# Pg05__Platform_Power.net
KiCad netlist of a schematic drawn in Altium Designer
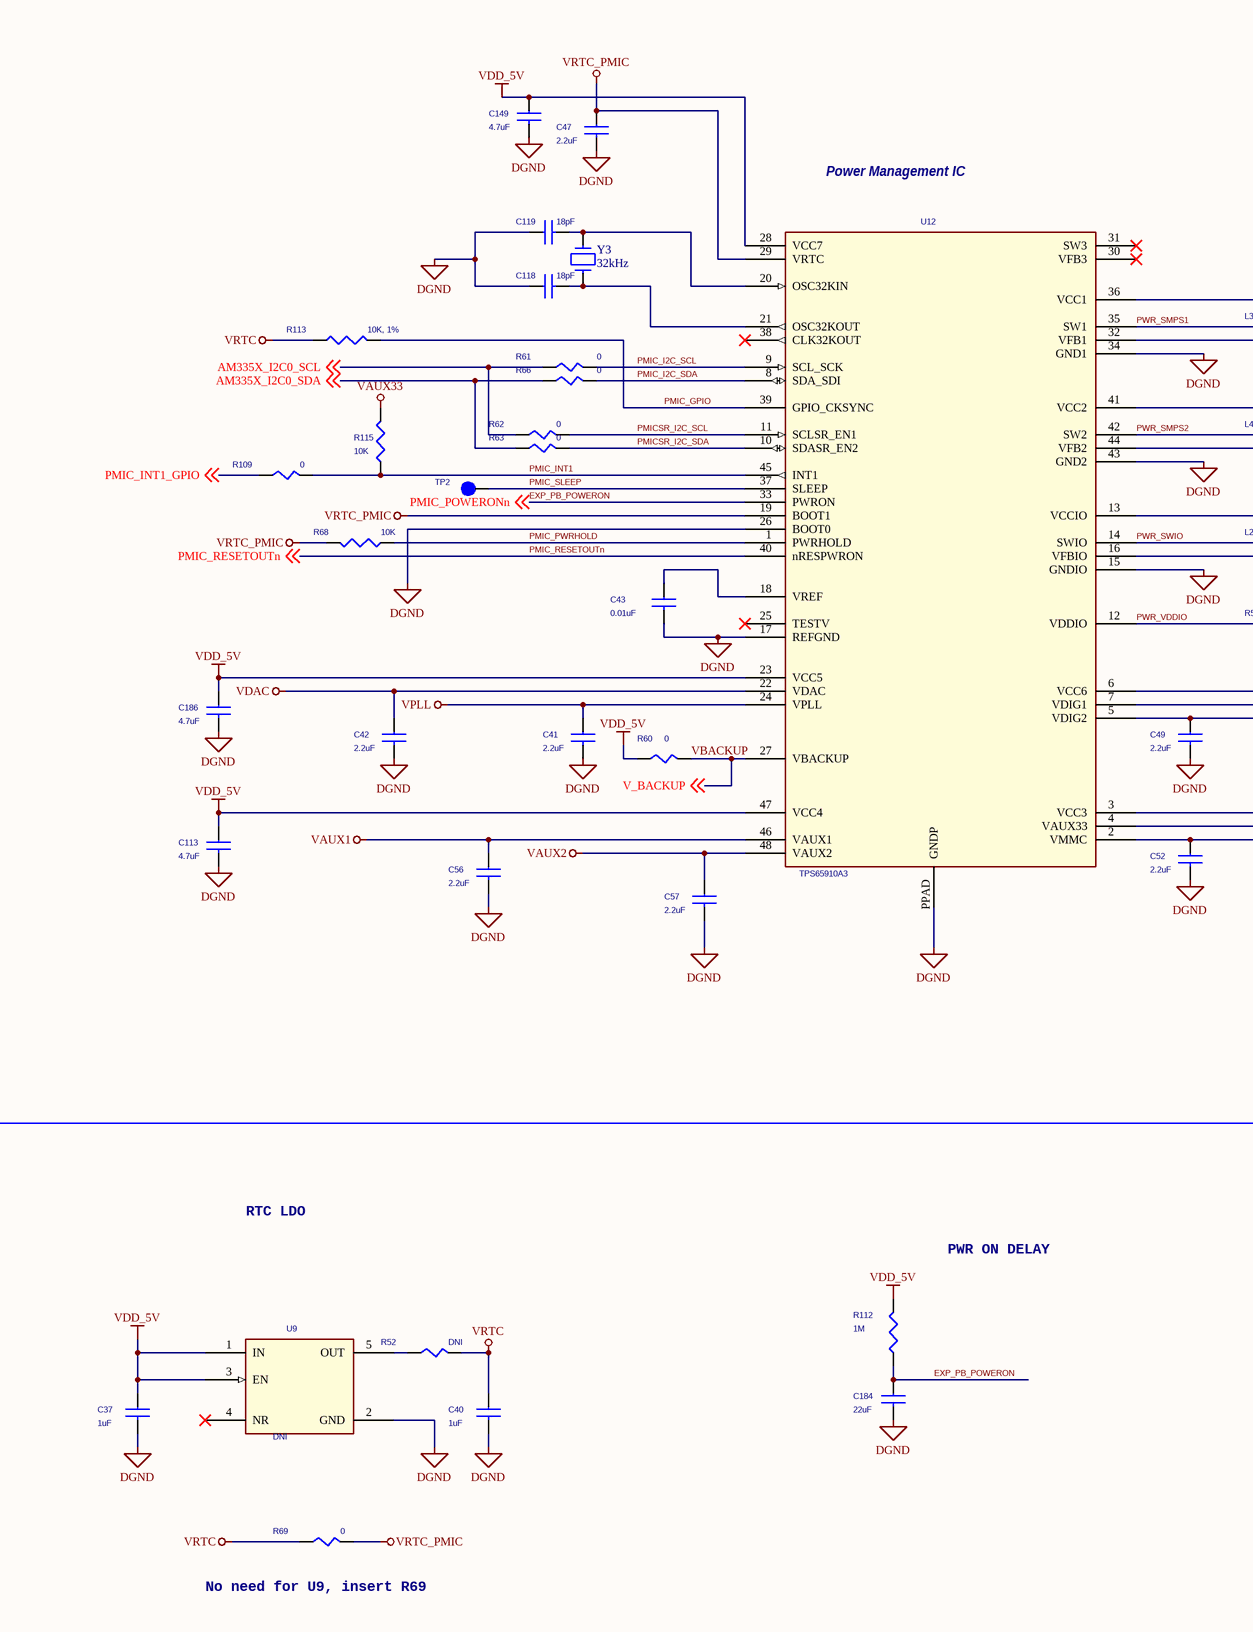
[diagram p0: Pg05_ Platform_Power.SchDoc, left]
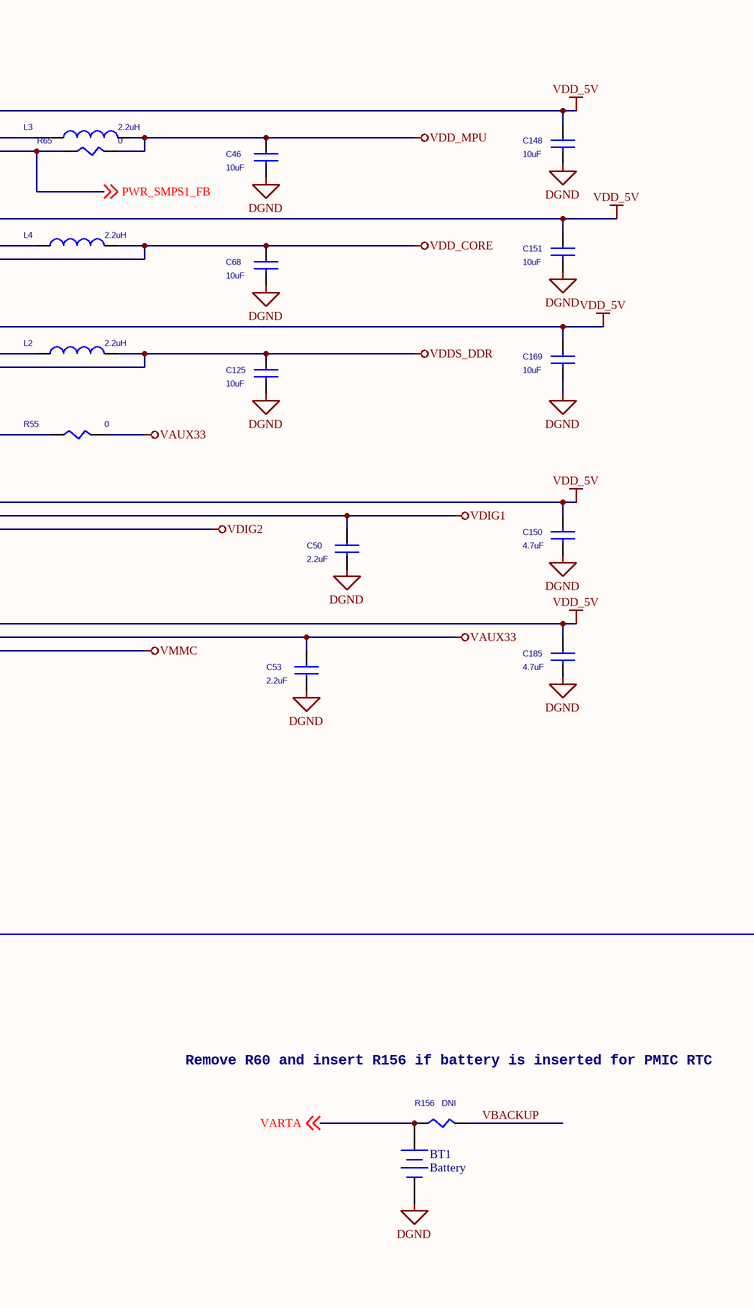
[diagram p1: Pg05_ Platform_Power.SchDoc, right]

(export (version "E")
  (design (tool "Eeschema 10.0.6"))
  (components
    (comp (ref "BT1")
      (value "Battery")
      (footprint "BAT_Varta12mm")
      (description "Multicell Battery")
      (fields (field (name "PUBLISHER") "Altium Limited"))
      (libsource (lib "Miscellaneous Devices") (part "Battery"))
    )
    (comp (ref "C37")
      (value "1uF")
      (footprint "SM-7351-CAP-0402")
      (fields (field (name "TIINTPARTNUMBER") "1C0084") (field (name "MFR") "AVX"))
      (libsource (lib "*") (part "1uFCapacitor10V10%0402"))
    )
    (comp (ref "C40")
      (value "1uF")
      (footprint "SM-7351-CAP-0402")
      (fields (field (name "TIINTPARTNUMBER") "1C0084") (field (name "MFR") "AVX"))
      (libsource (lib "*") (part "1uFCapacitor10V10%0402"))
    )
    (comp (ref "C41")
      (value "2.2uF")
      (footprint "SM-7351-CAP-0402")
      (description "Capacitor 2.2uF Ceramic, 6.3V, X5R, 20%")
      (fields (field (name "TIINTPARTNUMBER") "1C0091") (field (name "MFR") "Taiyo Yuden"))
      (libsource (lib "*") (part "2.2uFCapacitor6.3V20%smdX5R0402"))
    )
    (comp (ref "C42")
      (value "2.2uF")
      (footprint "SM-7351-CAP-0402")
      (description "Capacitor 2.2uF Ceramic, 6.3V, X5R, 20%")
      (fields (field (name "TIINTPARTNUMBER") "1C0091") (field (name "MFR") "Taiyo Yuden"))
      (libsource (lib "*") (part "2.2uFCapacitor6.3V20%smdX5R0402"))
    )
    (comp (ref "C43")
      (value "0.01uF")
      (footprint "SM-7351-CAP-0402")
      (fields (field (name "MFR") "Panasonic") (field (name "TIINTPARTNUMBER") "1C0012"))
      (libsource (lib "*") (part "0.01uFCapacitor16V10%0402_Dup1"))
    )
    (comp (ref "C46")
      (value "10uF")
      (footprint "SM-7351-CAP-0805")
      (description "Capacitor 10uF 16V 10% Ceramic 0805")
      (fields (field (name "MFR") "AVX") (field (name "TIINTPARTNUMBER") "1C0085"))
      (libsource (lib "*") (part "10uFCapacitor16V10%0805"))
    )
    (comp (ref "C47")
      (value "2.2uF")
      (footprint "SM-7351-CAP-0402")
      (description "Capacitor 2.2uF Ceramic, 6.3V, X5R, 20%")
      (fields (field (name "TIINTPARTNUMBER") "1C0091") (field (name "MFR") "Taiyo Yuden"))
      (libsource (lib "*") (part "2.2uFCapacitor6.3V20%smdX5R0402"))
    )
    (comp (ref "C49")
      (value "2.2uF")
      (footprint "SM-7351-CAP-0402")
      (description "Capacitor 2.2uF Ceramic, 6.3V, X5R, 20%")
      (fields (field (name "TIINTPARTNUMBER") "1C0091") (field (name "MFR") "Taiyo Yuden"))
      (libsource (lib "*") (part "2.2uFCapacitor6.3V20%smdX5R0402"))
    )
    (comp (ref "C50")
      (value "2.2uF")
      (footprint "SM-7351-CAP-0402")
      (description "Capacitor 2.2uF Ceramic, 6.3V, X5R, 20%")
      (fields (field (name "TIINTPARTNUMBER") "1C0091") (field (name "MFR") "Taiyo Yuden"))
      (libsource (lib "*") (part "2.2uFCapacitor6.3V20%smdX5R0402"))
    )
    (comp (ref "C52")
      (value "2.2uF")
      (footprint "SM-7351-CAP-0402")
      (description "Capacitor 2.2uF Ceramic, 6.3V, X5R, 20%")
      (fields (field (name "TIINTPARTNUMBER") "1C0091") (field (name "MFR") "Taiyo Yuden"))
      (libsource (lib "*") (part "2.2uFCapacitor6.3V20%smdX5R0402"))
    )
    (comp (ref "C53")
      (value "2.2uF")
      (footprint "SM-7351-CAP-0402")
      (description "Capacitor 2.2uF Ceramic, 6.3V, X5R, 20%")
      (fields (field (name "TIINTPARTNUMBER") "1C0091") (field (name "MFR") "Taiyo Yuden"))
      (libsource (lib "*") (part "2.2uFCapacitor6.3V20%smdX5R0402"))
    )
    (comp (ref "C56")
      (value "2.2uF")
      (footprint "SM-7351-CAP-0402")
      (description "Capacitor 2.2uF Ceramic, 6.3V, X5R, 20%")
      (fields (field (name "TIINTPARTNUMBER") "1C0091") (field (name "MFR") "Taiyo Yuden"))
      (libsource (lib "*") (part "2.2uFCapacitor6.3V20%smdX5R0402"))
    )
    (comp (ref "C57")
      (value "2.2uF")
      (footprint "SM-7351-CAP-0402")
      (description "Capacitor 2.2uF Ceramic, 6.3V, X5R, 20%")
      (fields (field (name "TIINTPARTNUMBER") "1C0091") (field (name "MFR") "Taiyo Yuden"))
      (libsource (lib "*") (part "2.2uFCapacitor6.3V20%smdX5R0402"))
    )
    (comp (ref "C68")
      (value "10uF")
      (footprint "SM-7351-CAP-0805")
      (description "Capacitor 10uF 16V 10% Ceramic 0805")
      (fields (field (name "MFR") "AVX") (field (name "TIINTPARTNUMBER") "1C0085"))
      (libsource (lib "*") (part "10uFCapacitor16V10%0805"))
    )
    (comp (ref "C113")
      (value "4.7uF")
      (footprint "SM-7351-CAP-0603")
      (fields (field (name "TIINTPARTNUMBER") "1C0103") (field (name "MFR") "Taiyo Yuden"))
      (libsource (lib "*") (part "4.7uFCapacitor16V10%0603"))
    )
    (comp (ref "C118")
      (value "18pF")
      (footprint "SM-7351-CAP-0402")
      (description "Capacitor 22pF 50V 10% 0402")
      (fields (field (name "MFR") "Panasonic") (field (name "TIINTPARTNUMBER") "1C0020"))
      (libsource (lib "*") (part "22pFCapacitor50V10%SMD0402"))
    )
    (comp (ref "C119")
      (value "18pF")
      (footprint "SM-7351-CAP-0402")
      (description "Capacitor 22pF 50V 10% 0402")
      (fields (field (name "MFR") "Panasonic") (field (name "TIINTPARTNUMBER") "1C0020"))
      (libsource (lib "*") (part "22pFCapacitor50V10%SMD0402"))
    )
    (comp (ref "C125")
      (value "10uF")
      (footprint "SM-7351-CAP-0805")
      (description "Capacitor 10uF 16V 10% Ceramic 0805")
      (fields (field (name "MFR") "AVX") (field (name "TIINTPARTNUMBER") "1C0085"))
      (libsource (lib "*") (part "10uFCapacitor16V10%0805"))
    )
    (comp (ref "C148")
      (value "10uF")
      (footprint "SM-7351-CAP-0805")
      (description "Capacitor 10uF 16V 10% Ceramic 0805")
      (fields (field (name "MFR") "AVX") (field (name "TIINTPARTNUMBER") "1C0085"))
      (libsource (lib "*") (part "10uFCapacitor16V10%0805"))
    )
    (comp (ref "C149")
      (value "4.7uF")
      (footprint "SM-7351-CAP-0603")
      (fields (field (name "TIINTPARTNUMBER") "1C0103") (field (name "MFR") "Taiyo Yuden"))
      (libsource (lib "*") (part "4.7uFCapacitor16V10%0603"))
    )
    (comp (ref "C150")
      (value "4.7uF")
      (footprint "SM-7351-CAP-0603")
      (fields (field (name "TIINTPARTNUMBER") "1C0103") (field (name "MFR") "Taiyo Yuden"))
      (libsource (lib "*") (part "4.7uFCapacitor16V10%0603"))
    )
    (comp (ref "C151")
      (value "10uF")
      (footprint "SM-7351-CAP-0805")
      (description "Capacitor 10uF 16V 10% Ceramic 0805")
      (fields (field (name "MFR") "AVX") (field (name "TIINTPARTNUMBER") "1C0085"))
      (libsource (lib "*") (part "10uFCapacitor16V10%0805"))
    )
    (comp (ref "C169")
      (value "10uF")
      (footprint "SM-7351-CAP-0805")
      (description "Capacitor 10uF 16V 10% Ceramic 0805")
      (fields (field (name "MFR") "AVX") (field (name "TIINTPARTNUMBER") "1C0085"))
      (libsource (lib "*") (part "10uFCapacitor16V10%0805"))
    )
    (comp (ref "C184")
      (value "22uF")
      (footprint "1206")
      (description "Capacitor 10uF 16V 10% Ceramic 0805")
      (fields (field (name "MFR") "AVX") (field (name "TIINTPARTNUMBER") "1C0085"))
      (libsource (lib "*") (part "10uFCapacitor16V10%0805"))
    )
    (comp (ref "C185")
      (value "4.7uF")
      (footprint "SM-7351-CAP-0603")
      (fields (field (name "TIINTPARTNUMBER") "1C0103") (field (name "MFR") "Taiyo Yuden"))
      (libsource (lib "*") (part "4.7uFCapacitor16V10%0603"))
    )
    (comp (ref "C186")
      (value "4.7uF")
      (footprint "SM-7351-CAP-0603")
      (fields (field (name "TIINTPARTNUMBER") "1C0103") (field (name "MFR") "Taiyo Yuden"))
      (libsource (lib "*") (part "4.7uFCapacitor16V10%0603"))
    )
    (comp (ref "L2")
      (value "2.2uH")
      (footprint "VLCF5020T")
      (fields (field (name "MFR") "TDK") (field (name "TIINTPARTNUMBER") "1L0025"))
      (libsource (lib "*") (part "2.2uHInductor10%2_1.6Asmd"))
    )
    (comp (ref "L3")
      (value "2.2uH")
      (footprint "VLCF5020T")
      (fields (field (name "MFR") "TDK") (field (name "TIINTPARTNUMBER") "1L0025"))
      (libsource (lib "*") (part "2.2uHInductor10%2_0.6Asmd"))
    )
    (comp (ref "L4")
      (value "2.2uH")
      (footprint "VLCF5020T")
      (fields (field (name "MFR") "TDK") (field (name "TIINTPARTNUMBER") "1L0025"))
      (libsource (lib "*") (part "2.2uHInductor10%2_1.6Asmd"))
    )
    (comp (ref "R52")
      (value "DNI")
      (footprint "SM-7351-RES-0603")
      (description "Resistor Zero ohm Jumper 0603")
      (fields (field (name "TIINTPARTNUMBER") "1R0096") (field (name "MFR") "Panasonic"))
      (libsource (lib "*") (part "ZeroOhmResistor1/16W0603"))
    )
    (comp (ref "R55")
      (value "0")
      (footprint "SM-7351-RES-0603")
      (description "Resistor Zero ohm Jumper 0603")
      (fields (field (name "MFR") "Panasonic") (field (name "TIINTPARTNUMBER") "1R0096"))
      (libsource (lib "*") (part "ZeroOhmResistor1/16W0603_Dup1"))
    )
    (comp (ref "R60")
      (value "0")
      (footprint "SM-7351-RES-0402")
      (description "Resistor Zero ohm Jumper 0402")
      (fields (field (name "TIINTPARTNUMBER") "1R0098") (field (name "MFR") "Panasonic"))
      (libsource (lib "*") (part "ZeroOhmResistor1/16W0402_Dup4"))
    )
    (comp (ref "R61")
      (value "0")
      (footprint "SM-7351-RES-0402")
      (description "Resistor Zero ohm Jumper 0402")
      (fields (field (name "TIINTPARTNUMBER") "1R0098") (field (name "MFR") "Panasonic"))
      (libsource (lib "*") (part "ZeroOhmResistor1/16W0402_Dup4"))
    )
    (comp (ref "R62")
      (value "0")
      (footprint "SM-7351-RES-0402")
      (description "Resistor Zero ohm Jumper 0402")
      (fields (field (name "TIINTPARTNUMBER") "1R0098") (field (name "MFR") "Panasonic"))
      (libsource (lib "*") (part "ZeroOhmResistor1/16W0402_Dup4"))
    )
    (comp (ref "R63")
      (value "0")
      (footprint "SM-7351-RES-0402")
      (description "Resistor Zero ohm Jumper 0402")
      (fields (field (name "TIINTPARTNUMBER") "1R0098") (field (name "MFR") "Panasonic"))
      (libsource (lib "*") (part "ZeroOhmResistor1/16W0402_Dup4"))
    )
    (comp (ref "R65")
      (value "0")
      (footprint "SM-7351-RES-0402")
      (description "Resistor Zero ohm Jumper 0402")
      (fields (field (name "TIINTPARTNUMBER") "1R0098") (field (name "MFR") "Panasonic"))
      (libsource (lib "*") (part "ZeroOhmResistor1/16W0402_Dup4"))
    )
    (comp (ref "R66")
      (value "0")
      (footprint "SM-7351-RES-0402")
      (description "Resistor Zero ohm Jumper 0402")
      (fields (field (name "TIINTPARTNUMBER") "1R0098") (field (name "MFR") "Panasonic"))
      (libsource (lib "*") (part "ZeroOhmResistor1/16W0402_Dup4"))
    )
    (comp (ref "R68")
      (value "10K")
      (footprint "SM-7351-RES-0402")
      (description "Resistor 10Kohm 1/16W 5% 0402")
      (fields (field (name "TIINTPARTNUMBER") "1R0168") (field (name "MFR") "Rohm"))
      (libsource (lib "*") (part "10KOhmResistor1/16W0402_Dup1"))
    )
    (comp (ref "R69")
      (value "0")
      (footprint "SM-7351-RES-0603")
      (description "Resistor Zero ohm Jumper 0603")
      (fields (field (name "TIINTPARTNUMBER") "1R0096") (field (name "MFR") "Panasonic"))
      (libsource (lib "*") (part "ZeroOhmResistor1/16W0603"))
    )
    (comp (ref "R109")
      (value "0")
      (footprint "SM-7351-RES-0402")
      (description "Resistor Zero ohm Jumper 0402")
      (fields (field (name "MFR") "Panasonic") (field (name "TIINTPARTNUMBER") "1R0098"))
      (libsource (lib "*") (part "ZeroOhmResistor1/16W0402_Dup2"))
    )
    (comp (ref "R112")
      (value "1M")
      (footprint "SM-7351-RES-0402")
      (description "Resistor 10Kohm 1/16W 5% 0402")
      (fields (field (name "TIINTPARTNUMBER") "1R0168") (field (name "MFR") "Rohm"))
      (libsource (lib "*") (part "10KOhmResistor1/16W0402_Dup1"))
    )
    (comp (ref "R113")
      (value "10K, 1%")
      (footprint "SM-7351-RES-0402")
      (fields (field (name "TIINTPARTNUMBER") "1R0254") (field (name "MFR") "PANASONIC-ECG"))
      (libsource (lib "*") (part "10KOhmResistor1/10W1%0402_Dup2"))
    )
    (comp (ref "R115")
      (value "10K")
      (footprint "SM-7351-RES-0402")
      (description "Resistor 10Kohm 1/16W 5% 0402")
      (fields (field (name "TIINTPARTNUMBER") "1R0168") (field (name "MFR") "Rohm"))
      (libsource (lib "*") (part "10KOhmResistor1/16W0402_Dup1"))
    )
    (comp (ref "R156")
      (value "DNI")
      (footprint "SM-7351-RES-0402")
      (description "Resistor Zero ohm Jumper 0402")
      (fields (field (name "TIINTPARTNUMBER") "1R0098") (field (name "MFR") "Panasonic"))
      (libsource (lib "*") (part "ZeroOhmResistor1/16W0402_Dup4"))
    )
    (comp (ref "TP2")
      (value "TP1mm")
      (footprint "tp_smd1mmcircle")
      (description "Testpoint SMD 1mm circle pad")
      (fields (field (name "TIINTPARTNUMBER") "2H0046"))
      (libsource (lib "*") (part "Testpoint_SMD1mmCircle"))
    )
    (comp (ref "U9")
      (value "DNI")
      (footprint "smdsc70-5")
      (description "Low Dropout 1.8V 150mA Linear Regulator")
      (fields (field (name "MFR") "TI") (field (name "TIINTPARTNUMBER") "1A0262"))
      (libsource (lib "*") (part "TPS71718"))
    )
    (comp (ref "U12")
      (value "TPS65910A3")
      (footprint "U_48_RSL")
      (fields (field (name "MFR") "TI") (field (name "TIINTPARTNUMBER") "1A0303"))
      (libsource (lib "*") (part "TPS65910A3"))
    )
    (comp (ref "Y3")
      (value "32kHz")
      (footprint "Xtal 3215")
      (description "CRYSTAL")
      (libsource (lib "Fireflash_B") (part "CRYSTAL"))
    )
  )
  (nets
    (net (code "1") (name "/PMICSR_I2C_SCL") (class "Default")
      (node (ref "R62") (pin "1") (pinfunction "P1_1") (pintype "passive"))
      (node (ref "U12") (pin "11") (pinfunction "SCLSR_EN1_11") (pintype "input"))
    )
    (net (code "2") (name "/PMICSR_I2C_SDA") (class "Default")
      (node (ref "R63") (pin "1") (pinfunction "P1_1") (pintype "passive"))
      (node (ref "U12") (pin "10") (pinfunction "SDASR_EN2_10") (pintype "bidirectional"))
    )
    (net (code "3") (name "/PMIC_GPIO") (class "Default")
      (node (ref "R113") (pin "2") (pinfunction "2_2") (pintype "passive"))
      (node (ref "U12") (pin "39") (pinfunction "GPIO_CKSYNC_39") (pintype "passive"))
    )
    (net (code "4") (name "/PMIC_I2C_SCL") (class "Default")
      (node (ref "R61") (pin "1") (pinfunction "P1_1") (pintype "passive"))
      (node (ref "U12") (pin "9") (pinfunction "SCL_SCK_9") (pintype "input"))
    )
    (net (code "5") (name "/PMIC_I2C_SDA") (class "Default")
      (node (ref "R66") (pin "1") (pinfunction "P1_1") (pintype "passive"))
      (node (ref "U12") (pin "8") (pinfunction "SDA_SDI_8") (pintype "bidirectional"))
    )
    (net (code "6") (name "/PMIC_INT1") (class "Default")
      (node (ref "R109") (pin "1") (pinfunction "P1_1") (pintype "passive"))
      (node (ref "R115") (pin "1") (pinfunction "P1_1") (pintype "passive"))
      (node (ref "U12") (pin "45") (pinfunction "INT1_45") (pintype "output"))
    )
    (net (code "7") (name "/PMIC_PWRHOLD") (class "Default")
      (node (ref "R68") (pin "1") (pinfunction "P1_1") (pintype "passive"))
      (node (ref "U12") (pin "1") (pinfunction "PWRHOLD_1") (pintype "passive"))
    )
    (net (code "8") (name "/PMIC_SLEEP") (class "Default")
      (node (ref "TP2") (pin "1") (pinfunction "1_1") (pintype "passive"))
      (node (ref "U12") (pin "37") (pinfunction "SLEEP_37") (pintype "passive"))
    )
    (net (code "9") (name "/PWR_SMPS1") (class "Default")
      (node (ref "L3") (pin "1") (pinfunction "1_1") (pintype "passive"))
      (node (ref "U12") (pin "35") (pinfunction "SW1_35") (pintype "power_in"))
    )
    (net (code "10") (name "/PWR_SMPS2") (class "Default")
      (node (ref "L4") (pin "1") (pinfunction "1_1") (pintype "passive"))
      (node (ref "U12") (pin "42") (pinfunction "SW2_42") (pintype "power_in"))
    )
    (net (code "11") (name "/PWR_SWIO") (class "Default")
      (node (ref "L2") (pin "1") (pinfunction "1_1") (pintype "passive"))
      (node (ref "U12") (pin "14") (pinfunction "SWIO_14") (pintype "power_in"))
    )
    (net (code "12") (name "/PWR_VDDIO") (class "Default")
      (node (ref "R55") (pin "2") (pinfunction "P2_2") (pintype "passive"))
      (node (ref "U12") (pin "12") (pinfunction "VDDIO_12") (pintype "passive"))
    )
    (net (code "13") (name "AM335X_I2C0_SCL") (class "Default")
      (node (ref "R61") (pin "2") (pinfunction "P2_2") (pintype "passive"))
      (node (ref "R62") (pin "2") (pinfunction "P2_2") (pintype "passive"))
    )
    (net (code "14") (name "AM335X_I2C0_SDA") (class "Default")
      (node (ref "R63") (pin "2") (pinfunction "P2_2") (pintype "passive"))
      (node (ref "R66") (pin "2") (pinfunction "P2_2") (pintype "passive"))
    )
    (net (code "15") (name "DGND") (class "Default")
      (node (ref "BT1") (pin "2") (pinfunction "-_2") (pintype "passive"))
      (node (ref "C113") (pin "2") (pinfunction "2_2") (pintype "passive"))
      (node (ref "C118") (pin "1") (pinfunction "1_1") (pintype "passive"))
      (node (ref "C119") (pin "1") (pinfunction "1_1") (pintype "passive"))
      (node (ref "C125") (pin "2") (pinfunction "2_2") (pintype "passive"))
      (node (ref "C148") (pin "2") (pinfunction "2_2") (pintype "passive"))
      (node (ref "C149") (pin "2") (pinfunction "2_2") (pintype "passive"))
      (node (ref "C150") (pin "2") (pinfunction "2_2") (pintype "passive"))
      (node (ref "C151") (pin "2") (pinfunction "2_2") (pintype "passive"))
      (node (ref "C169") (pin "2") (pinfunction "2_2") (pintype "passive"))
      (node (ref "C184") (pin "2") (pinfunction "2_2") (pintype "passive"))
      (node (ref "C185") (pin "2") (pinfunction "2_2") (pintype "passive"))
      (node (ref "C186") (pin "2") (pinfunction "2_2") (pintype "passive"))
      (node (ref "C37") (pin "2") (pinfunction "2_2") (pintype "passive"))
      (node (ref "C40") (pin "2") (pinfunction "2_2") (pintype "passive"))
      (node (ref "C41") (pin "2") (pinfunction "2_2") (pintype "passive"))
      (node (ref "C42") (pin "2") (pinfunction "2_2") (pintype "passive"))
      (node (ref "C43") (pin "2") (pinfunction "2_2") (pintype "passive"))
      (node (ref "C46") (pin "2") (pinfunction "2_2") (pintype "passive"))
      (node (ref "C47") (pin "2") (pinfunction "2_2") (pintype "passive"))
      (node (ref "C49") (pin "2") (pinfunction "2_2") (pintype "passive"))
      (node (ref "C50") (pin "2") (pinfunction "2_2") (pintype "passive"))
      (node (ref "C52") (pin "2") (pinfunction "2_2") (pintype "passive"))
      (node (ref "C53") (pin "2") (pinfunction "2_2") (pintype "passive"))
      (node (ref "C56") (pin "2") (pinfunction "2_2") (pintype "passive"))
      (node (ref "C57") (pin "2") (pinfunction "2_2") (pintype "passive"))
      (node (ref "C68") (pin "2") (pinfunction "2_2") (pintype "passive"))
      (node (ref "U12") (pin "15") (pinfunction "GNDIO_15") (pintype "power_in"))
      (node (ref "U12") (pin "17") (pinfunction "REFGND_17") (pintype "power_in"))
      (node (ref "U12") (pin "26") (pinfunction "BOOT0_26") (pintype "passive"))
      (node (ref "U12") (pin "34") (pinfunction "GND1_34") (pintype "power_in"))
      (node (ref "U12") (pin "43") (pinfunction "GND2_43") (pintype "power_in"))
      (node (ref "U12") (pin "PPAD") (pinfunction "GNDP_PPAD") (pintype "power_in"))
      (node (ref "U9") (pin "2") (pinfunction "GND_2") (pintype "power_in"))
    )
    (net (code "16") (name "Net-(R52-P2)") (class "Default")
      (node (ref "R52") (pin "2") (pinfunction "P2_2") (pintype "passive"))
      (node (ref "U9") (pin "5") (pinfunction "OUT_5") (pintype "passive"))
    )
    (net (code "17") (name "Net-(U12-OSC32KIN)") (class "Default")
      (node (ref "C119") (pin "2") (pinfunction "2_2") (pintype "passive"))
      (node (ref "U12") (pin "20") (pinfunction "OSC32KIN_20") (pintype "input"))
      (node (ref "Y3") (pin "2") (pintype "passive"))
    )
    (net (code "18") (name "Net-(U12-OSC32KOUT)") (class "Default")
      (node (ref "C118") (pin "2") (pinfunction "2_2") (pintype "passive"))
      (node (ref "U12") (pin "21") (pinfunction "OSC32KOUT_21") (pintype "output"))
      (node (ref "Y3") (pin "1") (pintype "passive"))
    )
    (net (code "19") (name "Net-(U12-VREF)") (class "Default")
      (node (ref "C43") (pin "1") (pinfunction "1_1") (pintype "passive"))
      (node (ref "U12") (pin "18") (pinfunction "VREF_18") (pintype "passive"))
    )
    (net (code "20") (name "PMIC_INT1_GPIO") (class "Default")
      (node (ref "R109") (pin "2") (pinfunction "P2_2") (pintype "passive"))
    )
    (net (code "21") (name "PMIC_POWERONn") (class "Default")
      (node (ref "C184") (pin "1") (pinfunction "1_1") (pintype "passive"))
      (node (ref "R112") (pin "1") (pinfunction "P1_1") (pintype "passive"))
      (node (ref "U12") (pin "33") (pinfunction "PWRON_33") (pintype "passive"))
    )
    (net (code "22") (name "PMIC_RESETOUTn") (class "Default")
      (node (ref "U12") (pin "40") (pinfunction "nRESPWRON_40") (pintype "passive"))
    )
    (net (code "23") (name "PWR_SMPS1_FB") (class "Default")
      (node (ref "R65") (pin "2") (pinfunction "P2_2") (pintype "passive"))
      (node (ref "U12") (pin "32") (pinfunction "VFB1_32") (pintype "passive"))
    )
    (net (code "24") (name "VARTA") (class "Default")
      (node (ref "BT1") (pin "1") (pinfunction "+_1") (pintype "passive"))
      (node (ref "R156") (pin "2") (pinfunction "P2_2") (pintype "passive"))
    )
    (net (code "25") (name "VAUX1") (class "Default")
      (node (ref "C56") (pin "1") (pinfunction "1_1") (pintype "passive"))
      (node (ref "U12") (pin "46") (pinfunction "VAUX1_46") (pintype "power_in"))
    )
    (net (code "26") (name "VAUX2") (class "Default")
      (node (ref "C57") (pin "1") (pinfunction "1_1") (pintype "passive"))
      (node (ref "U12") (pin "48") (pinfunction "VAUX2_48") (pintype "power_in"))
    )
    (net (code "27") (name "VAUX33") (class "Default")
      (node (ref "C53") (pin "1") (pinfunction "1_1") (pintype "passive"))
      (node (ref "R115") (pin "2") (pinfunction "P2_2") (pintype "passive"))
      (node (ref "R55") (pin "1") (pinfunction "P1_1") (pintype "passive"))
      (node (ref "U12") (pin "4") (pinfunction "VAUX33_4") (pintype "power_in"))
    )
    (net (code "28") (name "VDAC") (class "Default")
      (node (ref "C42") (pin "1") (pinfunction "1_1") (pintype "passive"))
      (node (ref "U12") (pin "22") (pinfunction "VDAC_22") (pintype "power_in"))
    )
    (net (code "29") (name "VDDS_DDR") (class "Default")
      (node (ref "C125") (pin "1") (pinfunction "1_1") (pintype "passive"))
      (node (ref "L2") (pin "2") (pinfunction "2_2") (pintype "passive"))
      (node (ref "U12") (pin "16") (pinfunction "VFBIO_16") (pintype "passive"))
    )
    (net (code "30") (name "VDD_5V") (class "Default")
      (node (ref "C113") (pin "1") (pinfunction "1_1") (pintype "passive"))
      (node (ref "C148") (pin "1") (pinfunction "1_1") (pintype "passive"))
      (node (ref "C149") (pin "1") (pinfunction "1_1") (pintype "passive"))
      (node (ref "C150") (pin "1") (pinfunction "1_1") (pintype "passive"))
      (node (ref "C151") (pin "1") (pinfunction "1_1") (pintype "passive"))
      (node (ref "C169") (pin "1") (pinfunction "1_1") (pintype "passive"))
      (node (ref "C185") (pin "1") (pinfunction "1_1") (pintype "passive"))
      (node (ref "C186") (pin "1") (pinfunction "1_1") (pintype "passive"))
      (node (ref "C37") (pin "1") (pinfunction "1_1") (pintype "passive"))
      (node (ref "R112") (pin "2") (pinfunction "P2_2") (pintype "passive"))
      (node (ref "R60") (pin "2") (pinfunction "P2_2") (pintype "passive"))
      (node (ref "U12") (pin "13") (pinfunction "VCCIO_13") (pintype "power_in"))
      (node (ref "U12") (pin "23") (pinfunction "VCC5_23") (pintype "power_in"))
      (node (ref "U12") (pin "28") (pinfunction "VCC7_28") (pintype "passive"))
      (node (ref "U12") (pin "3") (pinfunction "VCC3_3") (pintype "power_in"))
      (node (ref "U12") (pin "36") (pinfunction "VCC1_36") (pintype "passive"))
      (node (ref "U12") (pin "41") (pinfunction "VCC2_41") (pintype "passive"))
      (node (ref "U12") (pin "47") (pinfunction "VCC4_47") (pintype "power_in"))
      (node (ref "U12") (pin "6") (pinfunction "VCC6_6") (pintype "passive"))
      (node (ref "U9") (pin "1") (pinfunction "IN_1") (pintype "passive"))
      (node (ref "U9") (pin "3") (pinfunction "EN_3") (pintype "input"))
    )
    (net (code "31") (name "VDD_CORE") (class "Default")
      (node (ref "C68") (pin "1") (pinfunction "1_1") (pintype "passive"))
      (node (ref "L4") (pin "2") (pinfunction "2_2") (pintype "passive"))
      (node (ref "U12") (pin "44") (pinfunction "VFB2_44") (pintype "passive"))
    )
    (net (code "32") (name "VDD_MPU") (class "Default")
      (node (ref "C46") (pin "1") (pinfunction "1_1") (pintype "passive"))
      (node (ref "L3") (pin "2") (pinfunction "2_2") (pintype "passive"))
      (node (ref "R65") (pin "1") (pinfunction "P1_1") (pintype "passive"))
    )
    (net (code "33") (name "VDIG1") (class "Default")
      (node (ref "C50") (pin "1") (pinfunction "1_1") (pintype "passive"))
      (node (ref "U12") (pin "7") (pinfunction "VDIG1_7") (pintype "passive"))
    )
    (net (code "34") (name "VDIG2") (class "Default")
      (node (ref "C49") (pin "1") (pinfunction "1_1") (pintype "passive"))
      (node (ref "U12") (pin "5") (pinfunction "VDIG2_5") (pintype "passive"))
    )
    (net (code "35") (name "VMMC") (class "Default")
      (node (ref "C52") (pin "1") (pinfunction "1_1") (pintype "passive"))
      (node (ref "U12") (pin "2") (pinfunction "VMMC_2") (pintype "power_in"))
    )
    (net (code "36") (name "VPLL") (class "Default")
      (node (ref "C41") (pin "1") (pinfunction "1_1") (pintype "passive"))
      (node (ref "U12") (pin "24") (pinfunction "VPLL_24") (pintype "power_in"))
    )
    (net (code "37") (name "VRTC") (class "Default")
      (node (ref "C40") (pin "1") (pinfunction "1_1") (pintype "passive"))
      (node (ref "R113") (pin "1") (pinfunction "1_1") (pintype "passive"))
      (node (ref "R52") (pin "1") (pinfunction "P1_1") (pintype "passive"))
      (node (ref "R69") (pin "2") (pinfunction "P2_2") (pintype "passive"))
    )
    (net (code "38") (name "VRTC_PMIC") (class "Default")
      (node (ref "C47") (pin "1") (pinfunction "1_1") (pintype "passive"))
      (node (ref "R68") (pin "2") (pinfunction "P2_2") (pintype "passive"))
      (node (ref "R69") (pin "1") (pinfunction "P1_1") (pintype "passive"))
      (node (ref "U12") (pin "19") (pinfunction "BOOT1_19") (pintype "passive"))
      (node (ref "U12") (pin "29") (pinfunction "VRTC_29") (pintype "passive"))
    )
    (net (code "39") (name "V_BACKUP") (class "Default")
      (node (ref "R156") (pin "1") (pinfunction "P1_1") (pintype "passive"))
      (node (ref "R60") (pin "1") (pinfunction "P1_1") (pintype "passive"))
      (node (ref "U12") (pin "27") (pinfunction "VBACKUP_27") (pintype "power_in"))
    )
    (net (code "40") (name "unconnected-(U9-NR-Pad4)") (class "Default")
      (node (ref "U9") (pin "4") (pinfunction "NR_4") (pintype "passive+no_connect"))
    )
    (net (code "41") (name "unconnected-(U12-CLK32KOUT-Pad38)") (class "Default")
      (node (ref "U12") (pin "38") (pinfunction "CLK32KOUT_38") (pintype "output+no_connect"))
    )
    (net (code "42") (name "unconnected-(U12-SW3-Pad31)") (class "Default")
      (node (ref "U12") (pin "31") (pinfunction "SW3_31") (pintype "power_in+no_connect"))
    )
    (net (code "43") (name "unconnected-(U12-TESTV-Pad25)") (class "Default")
      (node (ref "U12") (pin "25") (pinfunction "TESTV_25") (pintype "passive+no_connect"))
    )
    (net (code "44") (name "unconnected-(U12-VFB3-Pad30)") (class "Default")
      (node (ref "U12") (pin "30") (pinfunction "VFB3_30") (pintype "passive+no_connect"))
    )
  )
)
